# Top_level.net
KiCad netlist of a schematic drawn in Altium Designer
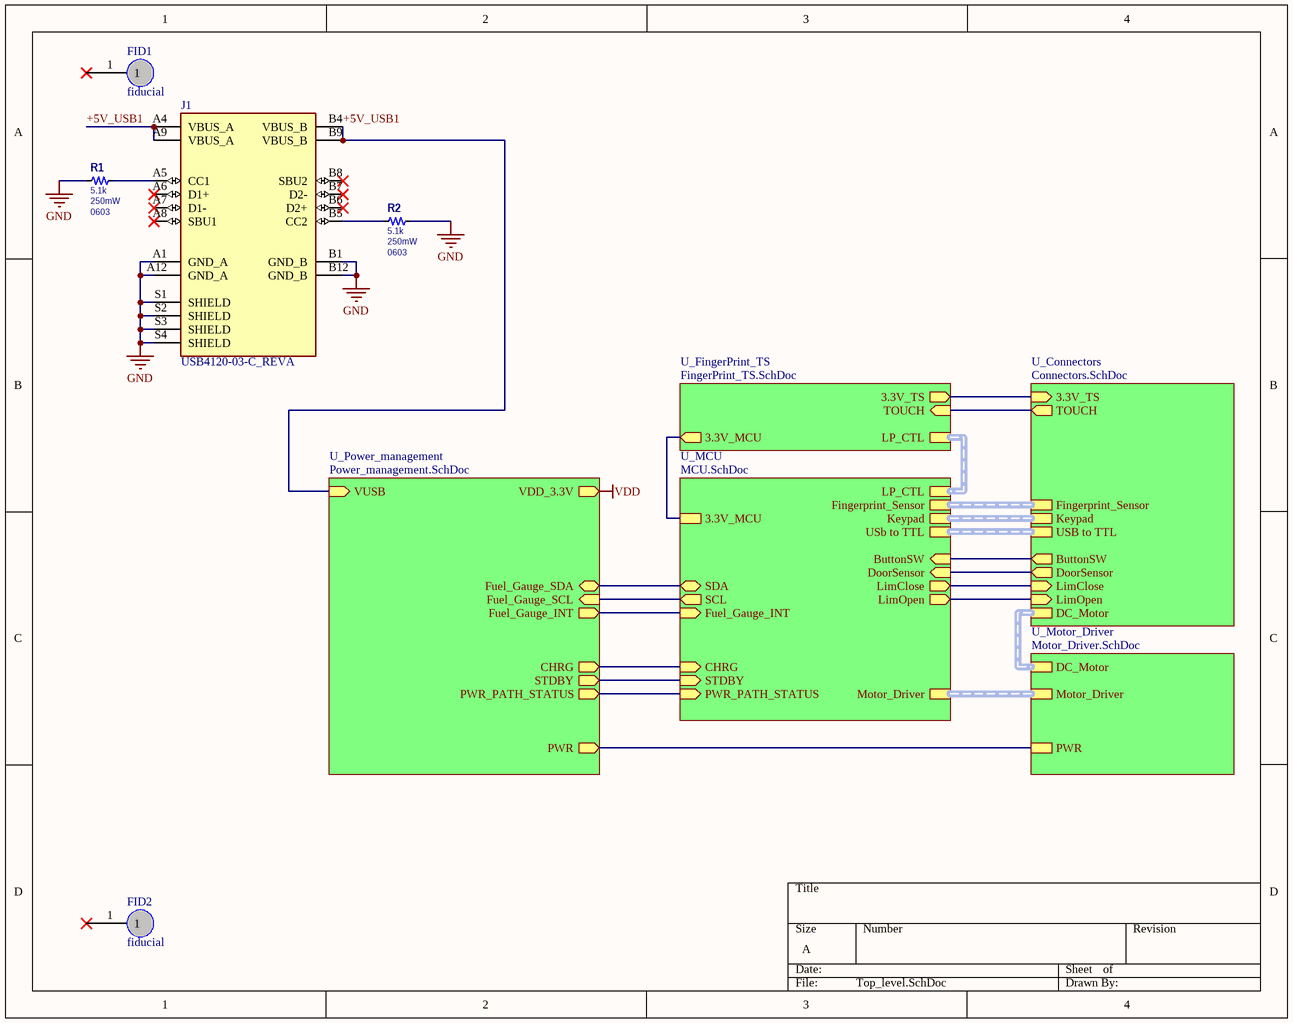
[diagram p0: Top_level.SchDoc]

(export (version "E")
  (design (tool "Eeschema 10.0.6"))
  (components
    (comp (ref "FID1")
      (value "fiducial")
      (footprint "Fiducial")
      (libsource (lib "Safety_Lock") (part "fiducial"))
    )
    (comp (ref "FID2")
      (value "fiducial")
      (footprint "Fiducial")
      (libsource (lib "Safety_Lock") (part "fiducial"))
    )
    (comp (ref "J1")
      (value "USB4120-03-C_REVA")
      (footprint "GCT_USB4120-03-C_REVA")
      (fields (field (name "MP") "USB4120-03-C") (field (name "MF") "Global Connector Technology"))
      (libsource (lib "Safety_Lock") (part "USB4120-03-C_REVA"))
    )
    (comp (ref "R1")
      (value "5.1k")
      (footprint "0603-R")
      (fields
        (field (name "MANUFACTURER") "Panasonic")
        (field (name "MANUFACTURER PART NUMBER") "ERJ-8GEYJ621V")
        (field (name "TOLERANCE") "5%")
        (field (name "POWER RATING") "250mW")
        (field (name "CASE/PACKAGE") "0603")
      )
      (libsource (lib "Safety_Lock") (part "Res"))
    )
    (comp (ref "R2")
      (value "5.1k")
      (footprint "0603-R")
      (fields
        (field (name "MANUFACTURER") "Panasonic")
        (field (name "MANUFACTURER PART NUMBER") "ERJ-8GEYJ621V")
        (field (name "TOLERANCE") "5%")
        (field (name "POWER RATING") "250mW")
        (field (name "CASE/PACKAGE") "0603")
      )
      (libsource (lib "Safety_Lock") (part "Res"))
    )
  )
  (nets
    (net (code "1") (name "/+5V_USB1") (class "Default")
      (node (ref "J1") (pin "A4") (pinfunction "VBUS_A_A4") (pintype "power_in"))
      (node (ref "J1") (pin "A9") (pinfunction "VBUS_A_A9") (pintype "power_in"))
      (node (ref "J1") (pin "B4") (pinfunction "VBUS_B_B4") (pintype "power_in"))
      (node (ref "J1") (pin "B9") (pinfunction "VBUS_B_B9") (pintype "power_in"))
    )
    (net (code "22") (name "GND") (class "Default")
      (node (ref "J1") (pin "A1") (pinfunction "GND_A_A1") (pintype "power_in"))
      (node (ref "J1") (pin "A12") (pinfunction "GND_A_A12") (pintype "power_in"))
      (node (ref "J1") (pin "B1") (pinfunction "GND_B_B1") (pintype "power_in"))
      (node (ref "J1") (pin "B12") (pinfunction "GND_B_B12") (pintype "power_in"))
      (node (ref "J1") (pin "S1") (pinfunction "SHIELD_S1") (pintype "passive"))
      (node (ref "J1") (pin "S2") (pinfunction "SHIELD_S2") (pintype "passive"))
      (node (ref "J1") (pin "S3") (pinfunction "SHIELD_S3") (pintype "passive"))
      (node (ref "J1") (pin "S4") (pinfunction "SHIELD_S4") (pintype "passive"))
      (node (ref "R1") (pin "1") (pinfunction "1_1") (pintype "passive"))
      (node (ref "R2") (pin "2") (pinfunction "2_2") (pintype "passive"))
    )
    (net (code "23") (name "Net-(J1-CC1)") (class "Default")
      (node (ref "J1") (pin "A5") (pinfunction "CC1_A5") (pintype "bidirectional"))
      (node (ref "R1") (pin "2") (pinfunction "2_2") (pintype "passive"))
    )
    (net (code "24") (name "Net-(J1-CC2)") (class "Default")
      (node (ref "J1") (pin "B5") (pinfunction "CC2_B5") (pintype "bidirectional"))
      (node (ref "R2") (pin "1") (pinfunction "1_1") (pintype "passive"))
    )
    (net (code "26") (name "unconnected-(FID1-Pad1)") (class "Default")
      (node (ref "FID1") (pin "1") (pinfunction "1_1") (pintype "passive+no_connect"))
    )
    (net (code "27") (name "unconnected-(FID2-Pad1)") (class "Default")
      (node (ref "FID2") (pin "1") (pinfunction "1_1") (pintype "passive+no_connect"))
    )
    (net (code "28") (name "unconnected-(J1-D1+-PadA6)") (class "Default")
      (node (ref "J1") (pin "A6") (pinfunction "D1+_A6") (pintype "bidirectional+no_connect"))
    )
    (net (code "29") (name "unconnected-(J1-D1--PadA7)") (class "Default")
      (node (ref "J1") (pin "A7") (pinfunction "D1-_A7") (pintype "bidirectional+no_connect"))
    )
    (net (code "30") (name "unconnected-(J1-D2+-PadB6)") (class "Default")
      (node (ref "J1") (pin "B6") (pinfunction "D2+_B6") (pintype "bidirectional+no_connect"))
    )
    (net (code "31") (name "unconnected-(J1-D2--PadB7)") (class "Default")
      (node (ref "J1") (pin "B7") (pinfunction "D2-_B7") (pintype "bidirectional+no_connect"))
    )
    (net (code "32") (name "unconnected-(J1-SBU1-PadA8)") (class "Default")
      (node (ref "J1") (pin "A8") (pinfunction "SBU1_A8") (pintype "bidirectional+no_connect"))
    )
    (net (code "33") (name "unconnected-(J1-SBU2-PadB8)") (class "Default")
      (node (ref "J1") (pin "B8") (pinfunction "SBU2_B8") (pintype "bidirectional+no_connect"))
    )
  )
)
